# classed.net
KiCad netlist of a schematic drawn in EAGLE
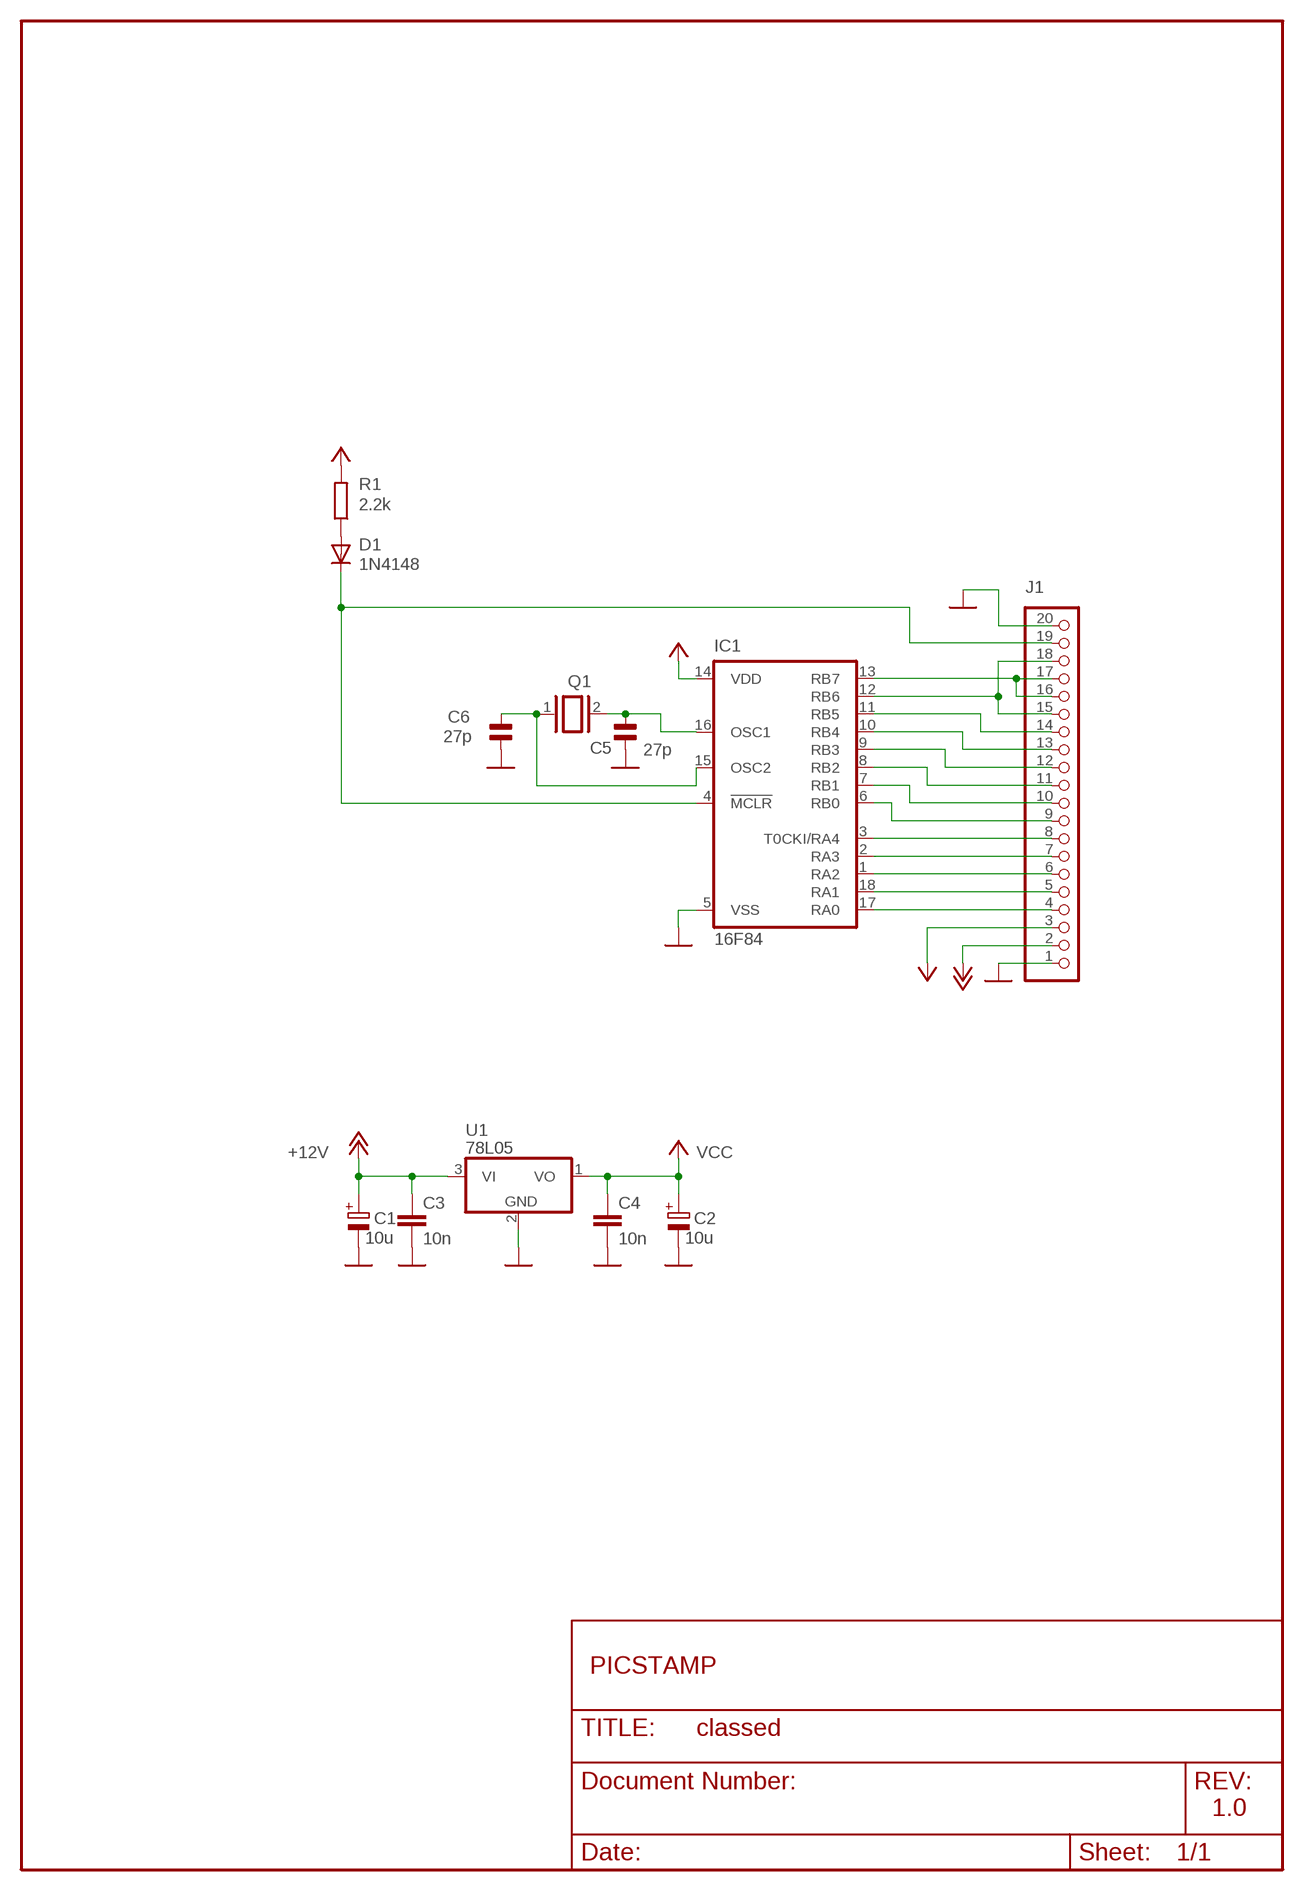
[diagram p0: schematic, sheet 1]

(export (version "E")
  (design (tool "Eeschema 10.0.6"))
  (components
    (comp (ref "C1")
      (value "10u")
      (footprint "eagle-import:E2,5-6")
      (libsource (lib "eagle-import") (part "E2,5-6"))
    )
    (comp (ref "C2")
      (value "10u")
      (footprint "eagle-import:E2,5-6")
      (libsource (lib "eagle-import") (part "E2,5-6"))
    )
    (comp (ref "C3")
      (value "10n")
      (footprint "eagle-import:C025-025X050")
      (libsource (lib "eagle-import") (part "C-EU025-025X050"))
    )
    (comp (ref "C4")
      (value "10n")
      (footprint "eagle-import:C025-025X050")
      (libsource (lib "eagle-import") (part "C-EU025-025X050"))
    )
    (comp (ref "C5")
      (value "27p")
      (footprint "eagle-import:C2,5-2")
      (libsource (lib "eagle-import") (part "C2.5/2"))
    )
    (comp (ref "C6")
      (value "27p")
      (footprint "eagle-import:C2,5-2")
      (libsource (lib "eagle-import") (part "C2.5/2"))
    )
    (comp (ref "D1")
      (value "1N4148")
      (footprint "eagle-import:DO35-10")
      (libsource (lib "eagle-import") (part "1N4148?"))
    )
    (comp (ref "IC1")
      (value "16F84")
      (footprint "eagle-import:DIL18")
      (libsource (lib "eagle-import") (part "PIC16F8P4A"))
    )
    (comp (ref "J1")
      (value "PINHD-1X20")
      (footprint "eagle-import:1X20")
      (libsource (lib "eagle-import") (part "PINHD-1X20"))
    )
    (comp (ref "Q1")
      (value "XTAL/S")
      (footprint "eagle-import:QS")
      (libsource (lib "eagle-import") (part "XTAL/S"))
    )
    (comp (ref "R1")
      (value "2.2k")
      (footprint "eagle-import:0207_10")
      (libsource (lib "eagle-import") (part "R-EU_0207/10"))
    )
    (comp (ref "U1")
      (value "78L05")
      (footprint "eagle-import:TO92")
      (libsource (lib "eagle-import") (part "78LXXZ"))
    )
  )
  (nets
    (net (code "1") (name "+12V") (class "Default")
      (node (ref "C1") (pin "+") (pinfunction "+_+") (pintype "passive"))
      (node (ref "C3") (pin "2") (pinfunction "2_2") (pintype "passive"))
      (node (ref "J1") (pin "2") (pinfunction "2_2") (pintype "passive"))
      (node (ref "U1") (pin "3") (pinfunction "VI_3") (pintype "input"))
    )
    (net (code "2") (name "GND") (class "Default")
      (node (ref "C1") (pin "-") (pinfunction "-_-") (pintype "passive"))
      (node (ref "C2") (pin "-") (pinfunction "-_-") (pintype "passive"))
      (node (ref "C3") (pin "1") (pinfunction "1_1") (pintype "passive"))
      (node (ref "C4") (pin "1") (pinfunction "1_1") (pintype "passive"))
      (node (ref "C5") (pin "1") (pinfunction "1_1") (pintype "passive"))
      (node (ref "C6") (pin "1") (pinfunction "1_1") (pintype "passive"))
      (node (ref "IC1") (pin "5") (pinfunction "VSS_5") (pintype "power_in"))
      (node (ref "J1") (pin "1") (pinfunction "1_1") (pintype "passive"))
      (node (ref "J1") (pin "20") (pinfunction "20_20") (pintype "passive"))
      (node (ref "U1") (pin "2") (pinfunction "GND_2") (pintype "passive"))
    )
    (net (code "3") (name "Net-(D1-C)") (class "Default")
      (node (ref "D1") (pin "K") (pinfunction "C_K") (pintype "passive"))
      (node (ref "IC1") (pin "4") (pinfunction "~{MCLR}_4") (pintype "input"))
      (node (ref "J1") (pin "19") (pinfunction "19_19") (pintype "passive"))
    )
    (net (code "4") (name "Net-(D1-PadA)") (class "Default")
      (node (ref "D1") (pin "A") (pinfunction "A_A") (pintype "passive"))
      (node (ref "R1") (pin "1") (pinfunction "1_1") (pintype "passive"))
    )
    (net (code "5") (name "Net-(IC1-OSC1)") (class "Default")
      (node (ref "C5") (pin "2") (pinfunction "2_2") (pintype "passive"))
      (node (ref "IC1") (pin "16") (pinfunction "OSC1_16") (pintype "input"))
      (node (ref "Q1") (pin "2") (pinfunction "2_2") (pintype "passive"))
    )
    (net (code "6") (name "Net-(IC1-OSC2)") (class "Default")
      (node (ref "C6") (pin "2") (pinfunction "2_2") (pintype "passive"))
      (node (ref "IC1") (pin "15") (pinfunction "OSC2_15") (pintype "output"))
      (node (ref "Q1") (pin "1") (pinfunction "1_1") (pintype "passive"))
    )
    (net (code "7") (name "Net-(IC1-RA0)") (class "Default")
      (node (ref "IC1") (pin "17") (pinfunction "RA0_17") (pintype "bidirectional"))
      (node (ref "J1") (pin "4") (pinfunction "4_4") (pintype "passive"))
    )
    (net (code "8") (name "Net-(IC1-RA1)") (class "Default")
      (node (ref "IC1") (pin "18") (pinfunction "RA1_18") (pintype "bidirectional"))
      (node (ref "J1") (pin "5") (pinfunction "5_5") (pintype "passive"))
    )
    (net (code "9") (name "Net-(IC1-RA2)") (class "Default")
      (node (ref "IC1") (pin "1") (pinfunction "RA2_1") (pintype "bidirectional"))
      (node (ref "J1") (pin "6") (pinfunction "6_6") (pintype "passive"))
    )
    (net (code "10") (name "Net-(IC1-RA3)") (class "Default")
      (node (ref "IC1") (pin "2") (pinfunction "RA3_2") (pintype "bidirectional"))
      (node (ref "J1") (pin "7") (pinfunction "7_7") (pintype "passive"))
    )
    (net (code "11") (name "Net-(IC1-RB0)") (class "Default")
      (node (ref "IC1") (pin "6") (pinfunction "RB0_6") (pintype "bidirectional"))
      (node (ref "J1") (pin "9") (pinfunction "9_9") (pintype "passive"))
    )
    (net (code "12") (name "Net-(IC1-RB1)") (class "Default")
      (node (ref "IC1") (pin "7") (pinfunction "RB1_7") (pintype "bidirectional"))
      (node (ref "J1") (pin "10") (pinfunction "10_10") (pintype "passive"))
    )
    (net (code "13") (name "Net-(IC1-RB2)") (class "Default")
      (node (ref "IC1") (pin "8") (pinfunction "RB2_8") (pintype "bidirectional"))
      (node (ref "J1") (pin "11") (pinfunction "11_11") (pintype "passive"))
    )
    (net (code "14") (name "Net-(IC1-RB3)") (class "Default")
      (node (ref "IC1") (pin "9") (pinfunction "RB3_9") (pintype "bidirectional"))
      (node (ref "J1") (pin "12") (pinfunction "12_12") (pintype "passive"))
    )
    (net (code "15") (name "Net-(IC1-RB4)") (class "Default")
      (node (ref "IC1") (pin "10") (pinfunction "RB4_10") (pintype "bidirectional"))
      (node (ref "J1") (pin "13") (pinfunction "13_13") (pintype "passive"))
    )
    (net (code "16") (name "Net-(IC1-RB5)") (class "Default")
      (node (ref "IC1") (pin "11") (pinfunction "RB5_11") (pintype "bidirectional"))
      (node (ref "J1") (pin "14") (pinfunction "14_14") (pintype "passive"))
    )
    (net (code "17") (name "Net-(IC1-RB6)") (class "Default")
      (node (ref "IC1") (pin "12") (pinfunction "RB6_12") (pintype "bidirectional"))
      (node (ref "J1") (pin "15") (pinfunction "15_15") (pintype "passive"))
      (node (ref "J1") (pin "18") (pinfunction "18_18") (pintype "passive"))
    )
    (net (code "18") (name "Net-(IC1-RB7)") (class "Default")
      (node (ref "IC1") (pin "13") (pinfunction "RB7_13") (pintype "bidirectional"))
      (node (ref "J1") (pin "16") (pinfunction "16_16") (pintype "passive"))
      (node (ref "J1") (pin "17") (pinfunction "17_17") (pintype "passive"))
    )
    (net (code "19") (name "Net-(IC1-T0CKI{slash}RA4)") (class "Default")
      (node (ref "IC1") (pin "3") (pinfunction "T0CKI/RA4_3") (pintype "bidirectional"))
      (node (ref "J1") (pin "8") (pinfunction "8_8") (pintype "passive"))
    )
    (net (code "20") (name "VCC") (class "Default")
      (node (ref "C2") (pin "+") (pinfunction "+_+") (pintype "passive"))
      (node (ref "C4") (pin "2") (pinfunction "2_2") (pintype "passive"))
      (node (ref "IC1") (pin "14") (pinfunction "VDD_14") (pintype "power_in"))
      (node (ref "J1") (pin "3") (pinfunction "3_3") (pintype "passive"))
      (node (ref "R1") (pin "2") (pinfunction "2_2") (pintype "passive"))
      (node (ref "U1") (pin "1") (pinfunction "VO_1") (pintype "output"))
    )
  )
)
